# ADC.net
KiCad netlist of a schematic drawn in Altium Designer
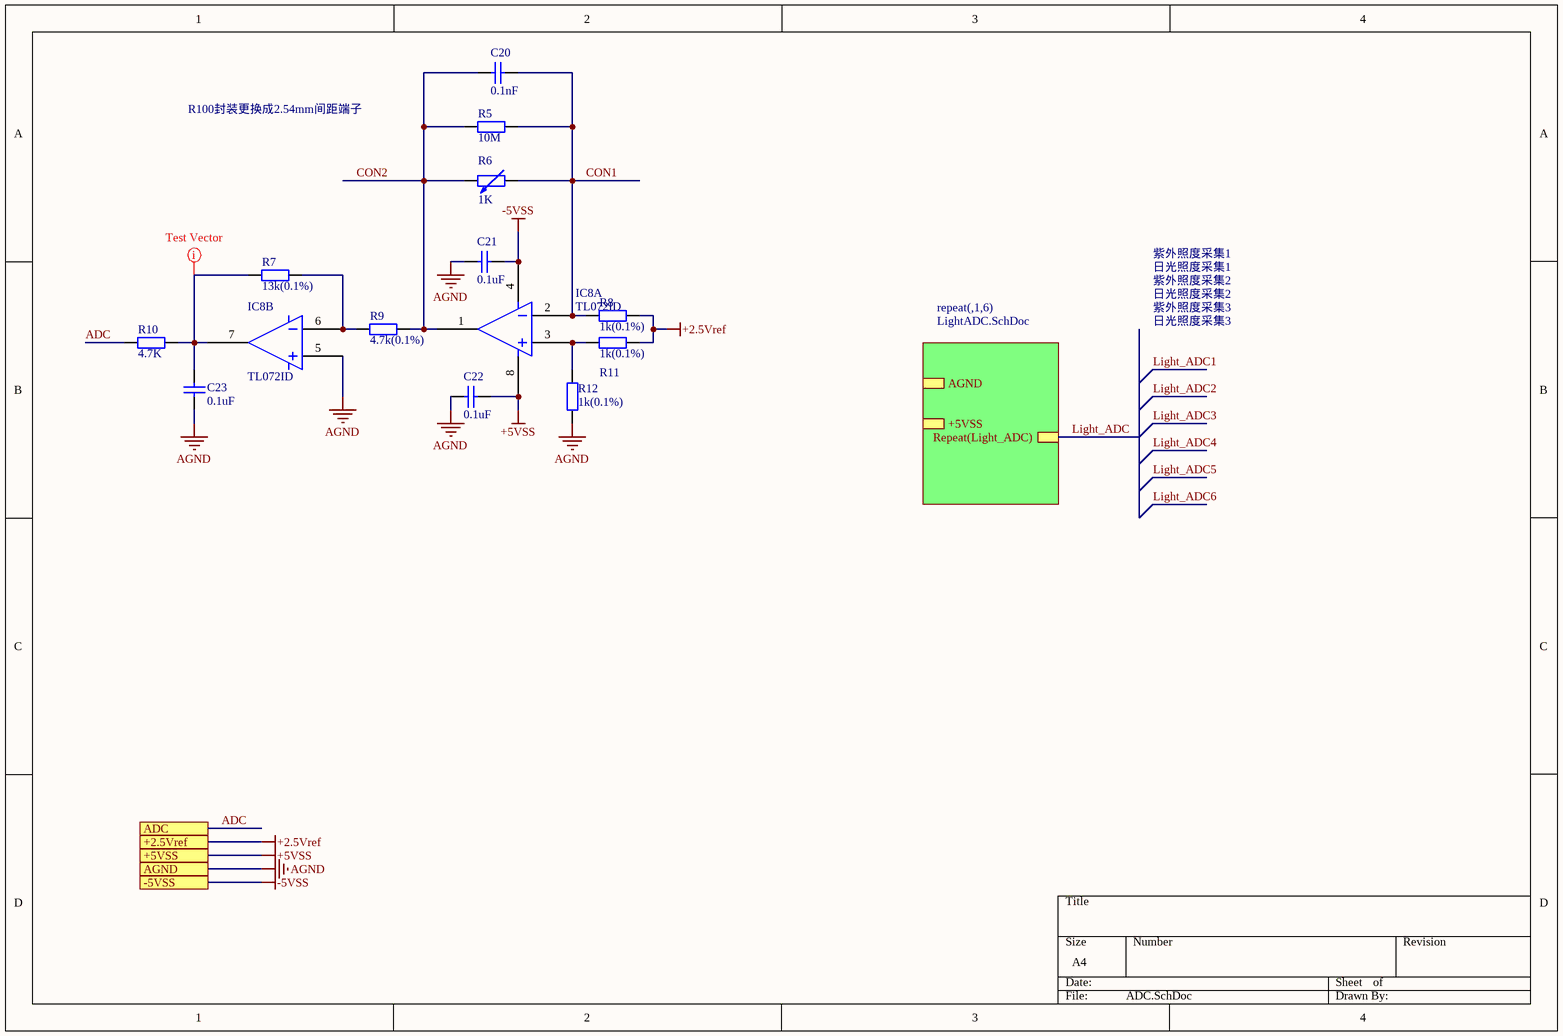
[diagram p0: ADC.SchDoc]

(export (version "E")
  (design (tool "Eeschema 10.0.6"))
  (components
    (comp (ref "C20")
      (value "0.1nF")
      (footprint "0603C")
      (description "Capacitor")
      (fields (field (name "PUBLISHER") "Altium Limited"))
      (libsource (lib "Miscellaneous Devices") (part "Cap"))
    )
    (comp (ref "C21")
      (value "0.1uF")
      (footprint "0603C")
      (description "Capacitor")
      (fields (field (name "PUBLISHER") "Altium Limited"))
      (libsource (lib "Miscellaneous Devices") (part "Cap"))
    )
    (comp (ref "C22")
      (value "0.1uF")
      (footprint "0603C")
      (description "Capacitor")
      (fields (field (name "PUBLISHER") "Altium Limited"))
      (libsource (lib "Miscellaneous Devices") (part "Cap"))
    )
    (comp (ref "C23")
      (value "0.1uF")
      (footprint "0603C")
      (description "Capacitor")
      (fields (field (name "PUBLISHER") "Altium Limited"))
      (libsource (lib "Miscellaneous Devices") (part "Cap"))
    )
    (comp (ref "IC8")
      (value "TL072ID")
      (footprint "SOP8")
      (libsource (lib "main board fo stk_1") (part "TL072_1"))
    )
    (comp (ref "R5")
      (value "10M")
      (footprint "0603R")
      (description "Resistor")
      (fields (field (name "PUBLISHER") "Altium Limited"))
      (libsource (lib "") (part "Res2_1"))
    )
    (comp (ref "R6")
      (value "1K")
      (footprint "F-DG141V-2.54-2P")
      (description "DG141V-2.54-2P")
      (fields (field (name "PUBLISHER") "Altium Limited"))
      (libsource (lib "Miscellaneous Devices") (part "Res Adj2"))
    )
    (comp (ref "R7")
      (value "13k(0.1%)")
      (footprint "0603R")
      (description "Resistor")
      (fields (field (name "PUBLISHER") "Altium Limited"))
      (libsource (lib "Miscellaneous Devices") (part "Res2"))
    )
    (comp (ref "R8")
      (value "1k(0.1%)")
      (footprint "0603R")
      (description "Resistor")
      (fields (field (name "PUBLISHER") "Altium Limited"))
      (libsource (lib "Miscellaneous Devices") (part "Res2"))
    )
    (comp (ref "R9")
      (value "4.7k(0.1%)")
      (footprint "0603R")
      (description "Resistor")
      (fields (field (name "PUBLISHER") "Altium Limited"))
      (libsource (lib "Miscellaneous Devices") (part "Res2"))
    )
    (comp (ref "R10")
      (value "4.7K")
      (footprint "0603R")
      (description "Resistor")
      (fields (field (name "PUBLISHER") "Altium Limited"))
      (libsource (lib "Miscellaneous Devices") (part "Res2"))
    )
    (comp (ref "R11")
      (value "1k(0.1%)")
      (footprint "0603R")
      (description "Resistor")
      (fields (field (name "PUBLISHER") "Altium Limited"))
      (libsource (lib "Miscellaneous Devices") (part "Res2"))
    )
    (comp (ref "R12")
      (value "1k(0.1%)")
      (footprint "0603R")
      (description "Resistor")
      (fields (field (name "PUBLISHER") "Altium Limited"))
      (libsource (lib "") (part "Res2_2"))
    )
  )
  (nets
    (net (code "1") (name "+2.5Vref") (class "Default")
      (node (ref "R11") (pin "1") (pinfunction "1_1") (pintype "passive"))
      (node (ref "R8") (pin "1") (pinfunction "1_1") (pintype "passive"))
    )
    (net (code "2") (name "+5VSS") (class "Default")
      (node (ref "C22") (pin "2") (pinfunction "2_2") (pintype "passive"))
      (node (ref "IC8") (pin "8") (pintype "passive"))
    )
    (net (code "3") (name "-5VSS") (class "Default")
      (node (ref "C21") (pin "2") (pinfunction "2_2") (pintype "passive"))
      (node (ref "IC8") (pin "4") (pintype "passive"))
    )
    (net (code "5") (name "/ADC") (class "Default")
      (node (ref "R10") (pin "2") (pinfunction "2_2") (pintype "passive"))
    )
    (net (code "7") (name "/CON1") (class "Default")
      (node (ref "C20") (pin "2") (pinfunction "2_2") (pintype "passive"))
      (node (ref "IC8") (pin "2") (pintype "passive"))
      (node (ref "R5") (pin "2") (pinfunction "2_2") (pintype "passive"))
      (node (ref "R6") (pin "1") (pinfunction "1_1") (pintype "passive"))
      (node (ref "R8") (pin "2") (pinfunction "2_2") (pintype "passive"))
    )
    (net (code "8") (name "/CON2") (class "Default")
      (node (ref "C20") (pin "1") (pinfunction "1_1") (pintype "passive"))
      (node (ref "IC8") (pin "1") (pintype "passive"))
      (node (ref "R5") (pin "1") (pinfunction "1_1") (pintype "passive"))
      (node (ref "R6") (pin "2") (pinfunction "2_2") (pintype "passive"))
      (node (ref "R9") (pin "1") (pinfunction "1_1") (pintype "passive"))
    )
    (net (code "16") (name "AGND") (class "Default")
      (node (ref "C21") (pin "1") (pinfunction "1_1") (pintype "passive"))
      (node (ref "C22") (pin "1") (pinfunction "1_1") (pintype "passive"))
      (node (ref "C23") (pin "1") (pinfunction "1_1") (pintype "passive"))
      (node (ref "IC8") (pin "5") (pintype "passive"))
      (node (ref "R12") (pin "2") (pinfunction "2_2") (pintype "passive"))
    )
    (net (code "17") (name "Net-(C23-Pad2)") (class "Default")
      (node (ref "C23") (pin "2") (pinfunction "2_2") (pintype "passive"))
      (node (ref "IC8") (pin "7") (pintype "passive"))
      (node (ref "R10") (pin "1") (pinfunction "1_1") (pintype "passive"))
      (node (ref "R7") (pin "2") (pinfunction "2_2") (pintype "passive"))
    )
    (net (code "18") (name "Net-(IC8-Pad3)") (class "Default")
      (node (ref "IC8") (pin "3") (pintype "passive"))
      (node (ref "R11") (pin "2") (pinfunction "2_2") (pintype "passive"))
      (node (ref "R12") (pin "1") (pinfunction "1_1") (pintype "passive"))
    )
    (net (code "19") (name "Net-(IC8-Pad6)") (class "Default")
      (node (ref "IC8") (pin "6") (pintype "passive"))
      (node (ref "R7") (pin "1") (pinfunction "1_1") (pintype "passive"))
      (node (ref "R9") (pin "2") (pinfunction "2_2") (pintype "passive"))
    )
  )
)
